# centralBoard.net
KiCad netlist of a schematic drawn in EAGLE
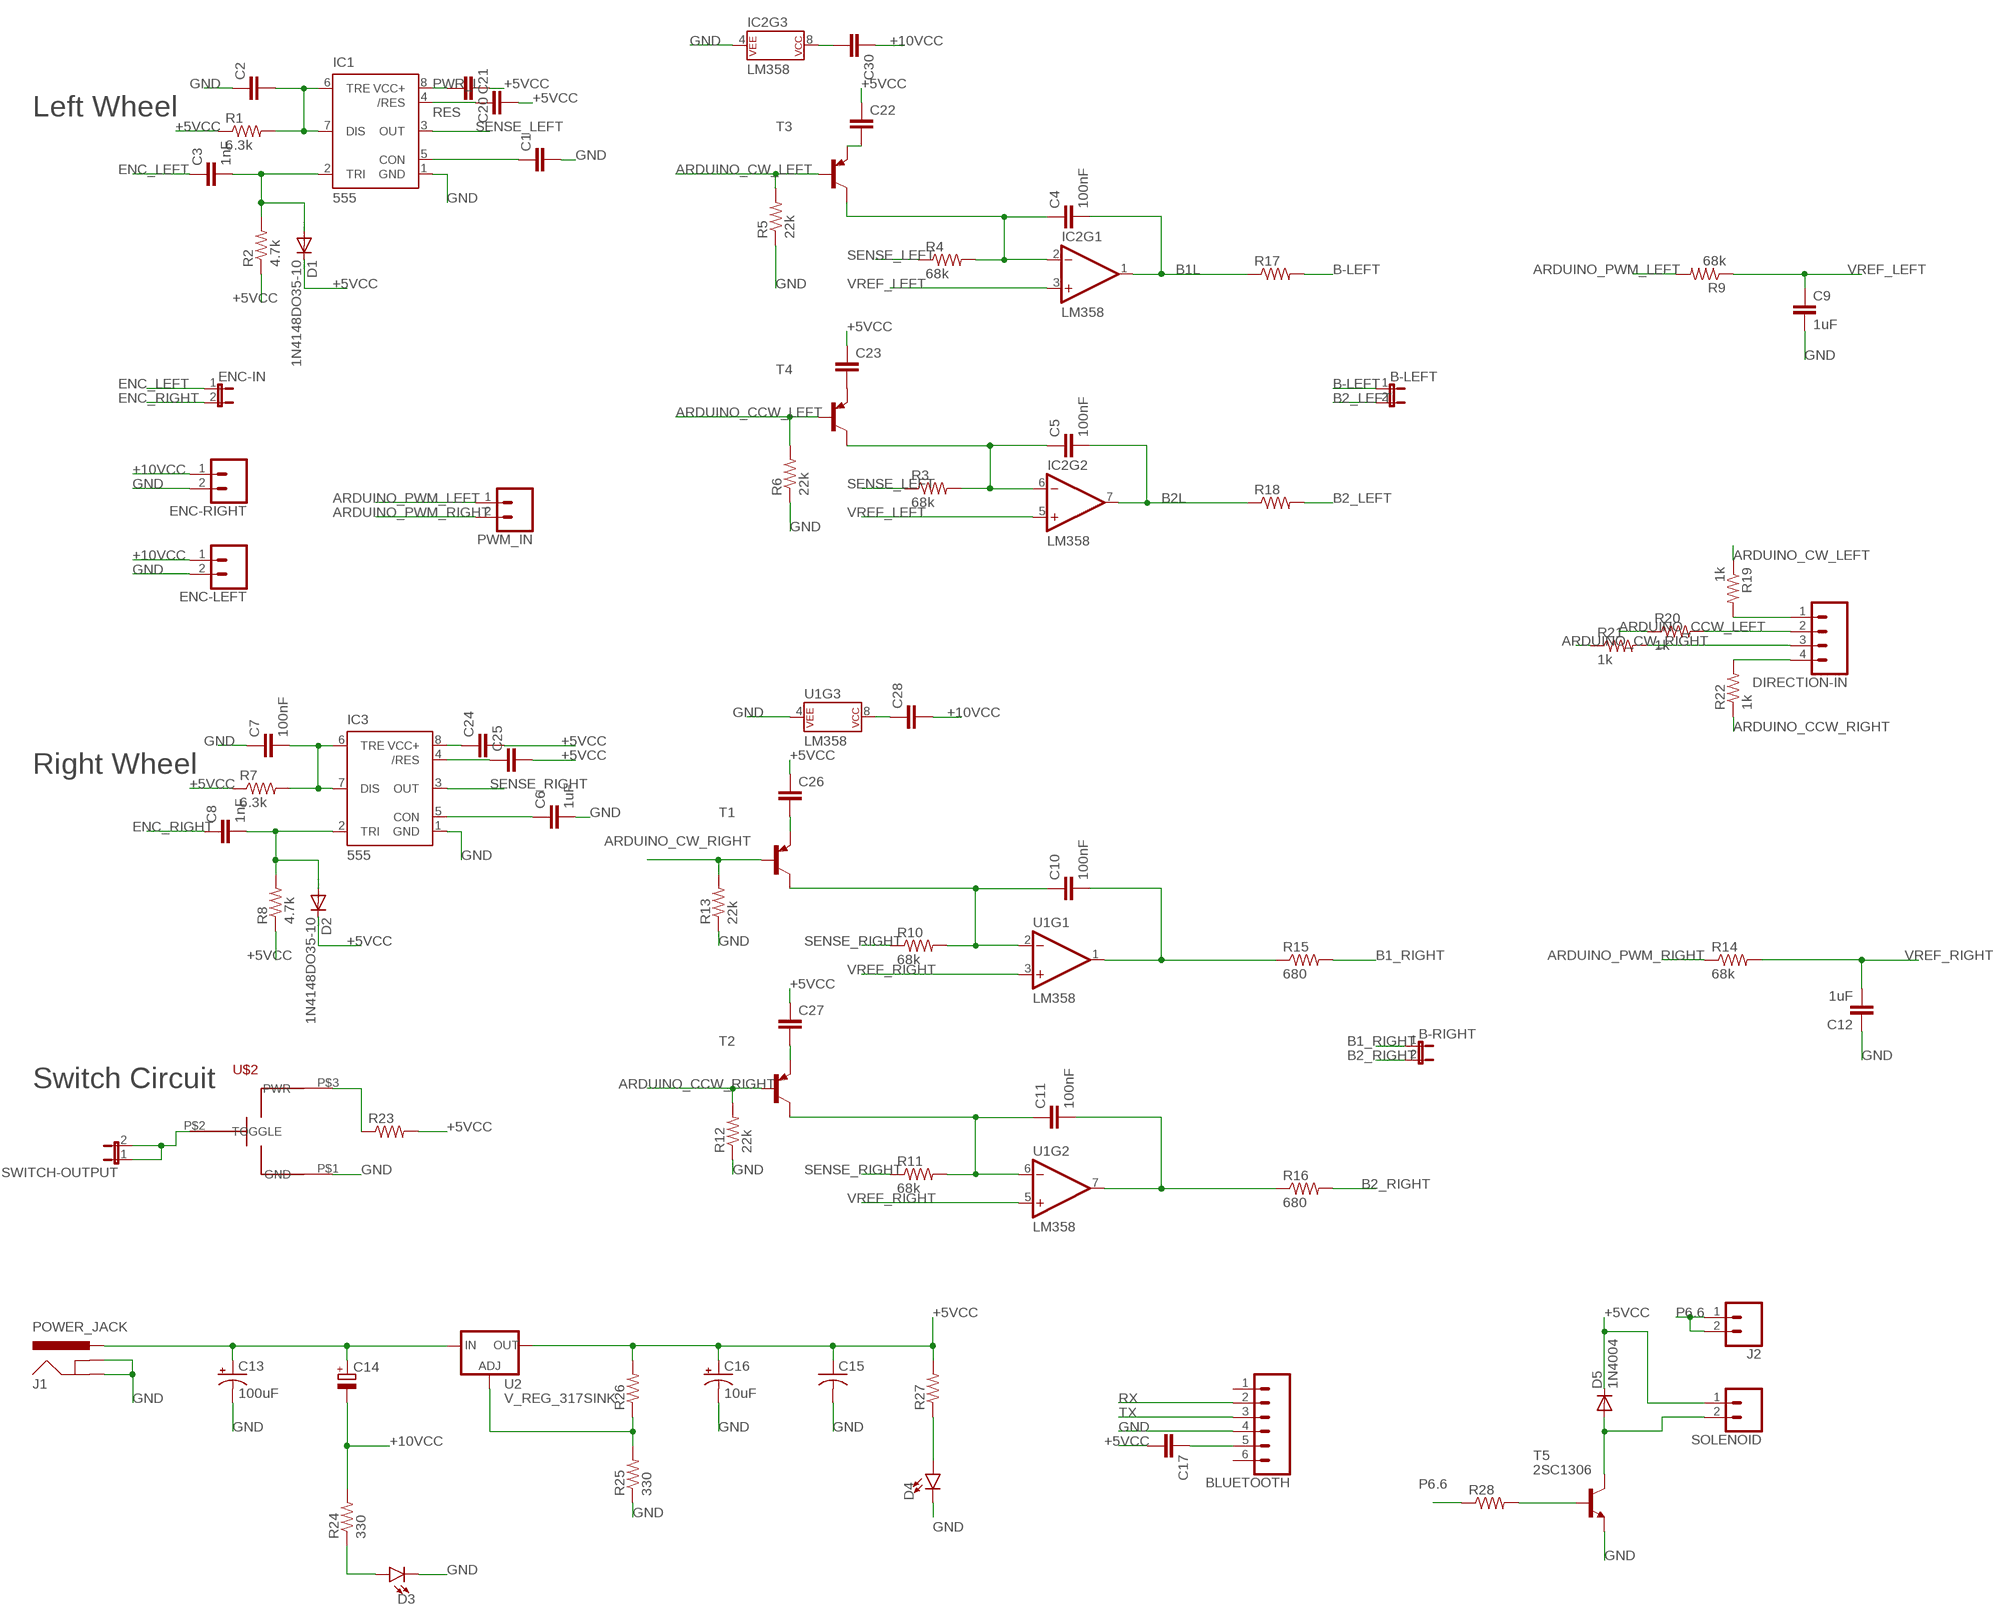
[diagram p0: schematic, sheet 1]

(export (version "E")
  (design (tool "Eeschema 10.0.6"))
  (components
    (comp (ref "B-LEFT")
      (value "JUMPER-2PTH")
      (footprint "eagle-import:1X02")
      (libsource (lib "eagle-import") (part "JUMPER-2PTH"))
    )
    (comp (ref "B-RIGHT")
      (value "JUMPER-2PTH")
      (footprint "eagle-import:1X02")
      (libsource (lib "eagle-import") (part "JUMPER-2PTH"))
    )
    (comp (ref "BLUETOOTH")
      (value "CONN_06SILK_FEMALE_PTH")
      (footprint "eagle-import:1X06")
      (libsource (lib "eagle-import") (part "CONN_06SILK_FEMALE_PTH"))
    )
    (comp (ref "C1")
      (value "C5/2.5")
      (footprint "eagle-import:C5B2.5")
      (libsource (lib "eagle-import") (part "C5/2.5"))
    )
    (comp (ref "C2")
      (value "C5/2.5")
      (footprint "eagle-import:C5B2.5")
      (libsource (lib "eagle-import") (part "C5/2.5"))
    )
    (comp (ref "C3")
      (value "1nF")
      (footprint "eagle-import:C5B2.5")
      (libsource (lib "eagle-import") (part "C5/2.5"))
    )
    (comp (ref "C4")
      (value "100nF")
      (footprint "eagle-import:C5B2.5")
      (libsource (lib "eagle-import") (part "C5/2.5"))
    )
    (comp (ref "C5")
      (value "100nF")
      (footprint "eagle-import:C5B2.5")
      (libsource (lib "eagle-import") (part "C5/2.5"))
    )
    (comp (ref "C6")
      (value "1uF")
      (footprint "eagle-import:C5B2.5")
      (libsource (lib "eagle-import") (part "C5/2.5"))
    )
    (comp (ref "C7")
      (value "100nF")
      (footprint "eagle-import:C5B2.5")
      (libsource (lib "eagle-import") (part "C5/2.5"))
    )
    (comp (ref "C8")
      (value "1nF")
      (footprint "eagle-import:C5B2.5")
      (libsource (lib "eagle-import") (part "C5/2.5"))
    )
    (comp (ref "C9")
      (value "1uF")
      (footprint "eagle-import:C5B2.5")
      (libsource (lib "eagle-import") (part "C5/2.5"))
    )
    (comp (ref "C10")
      (value "100nF")
      (footprint "eagle-import:C5B2.5")
      (libsource (lib "eagle-import") (part "C5/2.5"))
    )
    (comp (ref "C11")
      (value "100nF")
      (footprint "eagle-import:C5B2.5")
      (libsource (lib "eagle-import") (part "C5/2.5"))
    )
    (comp (ref "C12")
      (value "1uF")
      (footprint "eagle-import:C5B2.5")
      (libsource (lib "eagle-import") (part "C5/2.5"))
    )
    (comp (ref "C13")
      (value "100uF")
      (footprint "eagle-import:CPOL-RADIAL-2.5MM-6.5MM")
      (libsource (lib "eagle-import") (part "100UF-POLAR-RADIAL-2.5MM-25V-20%"))
    )
    (comp (ref "C14")
      (value "CPOL-EUE5-6")
      (footprint "eagle-import:E5-6")
      (libsource (lib "eagle-import") (part "CPOL-EUE5-6"))
    )
    (comp (ref "C15")
      (value "C-US050-030X075")
      (footprint "eagle-import:C050-030X075")
      (libsource (lib "eagle-import") (part "C-US050-030X075"))
    )
    (comp (ref "C16")
      (value "10uF")
      (footprint "eagle-import:CPOL-RADIAL-2.5MM-5MM")
      (libsource (lib "eagle-import") (part "10UF-POLAR-RADIAL-2.5MM-25V-20%"))
    )
    (comp (ref "C17")
      (value "C5/3")
      (footprint "eagle-import:C5B3")
      (libsource (lib "eagle-import") (part "C5/3"))
    )
    (comp (ref "C20")
      (value "C5/2.5")
      (footprint "eagle-import:C5B2.5")
      (libsource (lib "eagle-import") (part "C5/2.5"))
    )
    (comp (ref "C21")
      (value "C5/2.5")
      (footprint "eagle-import:C5B2.5")
      (libsource (lib "eagle-import") (part "C5/2.5"))
    )
    (comp (ref "C22")
      (value "C5/2.5")
      (footprint "eagle-import:C5B2.5")
      (libsource (lib "eagle-import") (part "C5/2.5"))
    )
    (comp (ref "C23")
      (value "C5/2.5")
      (footprint "eagle-import:C5B2.5")
      (libsource (lib "eagle-import") (part "C5/2.5"))
    )
    (comp (ref "C24")
      (value "C5/2.5")
      (footprint "eagle-import:C5B2.5")
      (libsource (lib "eagle-import") (part "C5/2.5"))
    )
    (comp (ref "C25")
      (value "C5/2.5")
      (footprint "eagle-import:C5B2.5")
      (libsource (lib "eagle-import") (part "C5/2.5"))
    )
    (comp (ref "C26")
      (value "C5/2.5")
      (footprint "eagle-import:C5B2.5")
      (libsource (lib "eagle-import") (part "C5/2.5"))
    )
    (comp (ref "C27")
      (value "C5/2.5")
      (footprint "eagle-import:C5B2.5")
      (libsource (lib "eagle-import") (part "C5/2.5"))
    )
    (comp (ref "C28")
      (value "C5/2.5")
      (footprint "eagle-import:C5B2.5")
      (libsource (lib "eagle-import") (part "C5/2.5"))
    )
    (comp (ref "C30")
      (value "C5/2.5")
      (footprint "eagle-import:C5B2.5")
      (libsource (lib "eagle-import") (part "C5/2.5"))
    )
    (comp (ref "D1")
      (value "1N4148DO35-10")
      (footprint "eagle-import:DO35-10")
      (libsource (lib "eagle-import") (part "1N4148DO35-10"))
    )
    (comp (ref "D2")
      (value "1N4148DO35-10")
      (footprint "eagle-import:DO35-10")
      (libsource (lib "eagle-import") (part "1N4148DO35-10"))
    )
    (comp (ref "D3")
      (value "LED-RED1206")
      (footprint "eagle-import:LED-1206")
      (libsource (lib "eagle-import") (part "LED-RED1206"))
    )
    (comp (ref "D4")
      (value "LED-RED1206")
      (footprint "eagle-import:LED-1206")
      (libsource (lib "eagle-import") (part "LED-RED1206"))
    )
    (comp (ref "D5")
      (value "1N4004")
      (footprint "eagle-import:DO41-10")
      (libsource (lib "eagle-import") (part "1N4004"))
    )
    (comp (ref "DIRECTION-IN")
      (value "CONN_04")
      (footprint "eagle-import:1X04")
      (libsource (lib "eagle-import") (part "CONN_04"))
    )
    (comp (ref "ENC-IN")
      (value "JUMPER-2PTH")
      (footprint "eagle-import:1X02")
      (libsource (lib "eagle-import") (part "JUMPER-2PTH"))
    )
    (comp (ref "ENC-LEFT")
      (value "CONN_02")
      (footprint "eagle-import:1X02")
      (libsource (lib "eagle-import") (part "CONN_02"))
    )
    (comp (ref "ENC-RIGHT")
      (value "CONN_02")
      (footprint "eagle-import:1X02")
      (libsource (lib "eagle-import") (part "CONN_02"))
    )
    (comp (ref "IC1")
      (value "555")
      (footprint "eagle-import:DIP08-KIT")
      (libsource (lib "eagle-import") (part "555KIT"))
    )
    (comp (ref "IC2")
      (value "LM358")
      (footprint "eagle-import:DIP08")
      (libsource (lib "eagle-import") (part "LM358"))
    )
    (comp (ref "IC3")
      (value "555")
      (footprint "eagle-import:DIP08-KIT")
      (libsource (lib "eagle-import") (part "555KIT"))
    )
    (comp (ref "J1")
      (value "POWER_JACK")
      (footprint "eagle-import:POWER_JACK_PTH")
      (libsource (lib "eagle-import") (part "POWER_JACK"))
    )
    (comp (ref "J2")
      (value "CONN_02")
      (footprint "eagle-import:1X02")
      (libsource (lib "eagle-import") (part "CONN_02"))
    )
    (comp (ref "PWM_IN")
      (value "CONN_02LOCK")
      (footprint "eagle-import:1X02_LOCK")
      (libsource (lib "eagle-import") (part "CONN_02LOCK"))
    )
    (comp (ref "R1")
      (value "6.3k")
      (footprint "eagle-import:0207_10")
      (libsource (lib "eagle-import") (part "R-US_0207/10"))
    )
    (comp (ref "R2")
      (value "4.7k")
      (footprint "eagle-import:0207_10")
      (libsource (lib "eagle-import") (part "R-US_0207/10"))
    )
    (comp (ref "R3")
      (value "68k")
      (footprint "eagle-import:0207_10")
      (libsource (lib "eagle-import") (part "R-US_0207/10"))
    )
    (comp (ref "R4")
      (value "68k")
      (footprint "eagle-import:0207_10")
      (libsource (lib "eagle-import") (part "R-US_0207/10"))
    )
    (comp (ref "R5")
      (value "22k")
      (footprint "eagle-import:0207_10")
      (libsource (lib "eagle-import") (part "R-US_0207/10"))
    )
    (comp (ref "R6")
      (value "22k")
      (footprint "eagle-import:0207_10")
      (libsource (lib "eagle-import") (part "R-US_0207/10"))
    )
    (comp (ref "R7")
      (value "6.3k")
      (footprint "eagle-import:0207_10")
      (libsource (lib "eagle-import") (part "R-US_0207/10"))
    )
    (comp (ref "R8")
      (value "4.7k")
      (footprint "eagle-import:0207_10")
      (libsource (lib "eagle-import") (part "R-US_0207/10"))
    )
    (comp (ref "R9")
      (value "68k")
      (footprint "eagle-import:0207_10")
      (libsource (lib "eagle-import") (part "R-US_0207/10"))
    )
    (comp (ref "R10")
      (value "68k")
      (footprint "eagle-import:0207_10")
      (libsource (lib "eagle-import") (part "R-US_0207/10"))
    )
    (comp (ref "R11")
      (value "68k")
      (footprint "eagle-import:0207_10")
      (libsource (lib "eagle-import") (part "R-US_0207/10"))
    )
    (comp (ref "R12")
      (value "22k")
      (footprint "eagle-import:0207_10")
      (libsource (lib "eagle-import") (part "R-US_0207/10"))
    )
    (comp (ref "R13")
      (value "22k")
      (footprint "eagle-import:0207_10")
      (libsource (lib "eagle-import") (part "R-US_0207/10"))
    )
    (comp (ref "R14")
      (value "68k")
      (footprint "eagle-import:0207_10")
      (libsource (lib "eagle-import") (part "R-US_0207/10"))
    )
    (comp (ref "R15")
      (value "680")
      (footprint "eagle-import:0207_10")
      (libsource (lib "eagle-import") (part "R-US_0207/10"))
    )
    (comp (ref "R16")
      (value "680")
      (footprint "eagle-import:0207_10")
      (libsource (lib "eagle-import") (part "R-US_0207/10"))
    )
    (comp (ref "R17")
      (value "R-US_0207/10")
      (footprint "eagle-import:0207_10")
      (libsource (lib "eagle-import") (part "R-US_0207/10"))
    )
    (comp (ref "R18")
      (value "R-US_0207/10")
      (footprint "eagle-import:0207_10")
      (libsource (lib "eagle-import") (part "R-US_0207/10"))
    )
    (comp (ref "R19")
      (value "1k")
      (footprint "eagle-import:0207_10")
      (libsource (lib "eagle-import") (part "R-US_0207/10"))
    )
    (comp (ref "R20")
      (value "1k")
      (footprint "eagle-import:0207_10")
      (libsource (lib "eagle-import") (part "R-US_0207/10"))
    )
    (comp (ref "R21")
      (value "1k")
      (footprint "eagle-import:0207_10")
      (libsource (lib "eagle-import") (part "R-US_0207/10"))
    )
    (comp (ref "R22")
      (value "1k")
      (footprint "eagle-import:0207_10")
      (libsource (lib "eagle-import") (part "R-US_0207/10"))
    )
    (comp (ref "R23")
      (value "R-US_0207/10")
      (footprint "eagle-import:0207_10")
      (libsource (lib "eagle-import") (part "R-US_0207/10"))
    )
    (comp (ref "R24")
      (value "330")
      (footprint "eagle-import:0207_10")
      (libsource (lib "eagle-import") (part "R-US_0207/10"))
    )
    (comp (ref "R25")
      (value "330")
      (footprint "eagle-import:0207_10")
      (libsource (lib "eagle-import") (part "R-US_0207/10"))
    )
    (comp (ref "R26")
      (value "R-US_0207/10")
      (footprint "eagle-import:0207_10")
      (libsource (lib "eagle-import") (part "R-US_0207/10"))
    )
    (comp (ref "R27")
      (value "R-US_0207/10")
      (footprint "eagle-import:0207_10")
      (libsource (lib "eagle-import") (part "R-US_0207/10"))
    )
    (comp (ref "R28")
      (value "R-US_0207/10")
      (footprint "eagle-import:0207_10")
      (libsource (lib "eagle-import") (part "R-US_0207/10"))
    )
    (comp (ref "SOLENOID")
      (value "CONN_02")
      (footprint "eagle-import:1X02")
      (libsource (lib "eagle-import") (part "CONN_02"))
    )
    (comp (ref "SWITCH-OUTPUT")
      (value "JUMPER-2PTH")
      (footprint "eagle-import:1X02")
      (libsource (lib "eagle-import") (part "JUMPER-2PTH"))
    )
    (comp (ref "T1")
      (value "2N4126-PNP-TO92-CBE")
      (footprint "eagle-import:TO92-CBE")
      (libsource (lib "eagle-import") (part "-PNP-TO92-CBE2N4126"))
    )
    (comp (ref "T2")
      (value "2N4126-PNP-TO92-CBE")
      (footprint "eagle-import:TO92-CBE")
      (libsource (lib "eagle-import") (part "-PNP-TO92-CBE2N4126"))
    )
    (comp (ref "T3")
      (value "2N4126-PNP-TO92-CBE")
      (footprint "eagle-import:TO92-CBE")
      (libsource (lib "eagle-import") (part "-PNP-TO92-CBE2N4126"))
    )
    (comp (ref "T4")
      (value "2N4126-PNP-TO92-CBE")
      (footprint "eagle-import:TO92-CBE")
      (libsource (lib "eagle-import") (part "-PNP-TO92-CBE2N4126"))
    )
    (comp (ref "T5")
      (value "2SC1306")
      (footprint "eagle-import:TO220BV")
      (libsource (lib "eagle-import") (part "2SC1306"))
    )
    (comp (ref "U$2")
      (value "SWITCH")
      (footprint "eagle-import:SWITCH")
      (libsource (lib "eagle-import") (part "SWITCH"))
    )
    (comp (ref "U1")
      (value "LM358")
      (footprint "eagle-import:DIP08")
      (libsource (lib "eagle-import") (part "LM358"))
    )
    (comp (ref "U2")
      (value "V_REG_317SINK")
      (footprint "eagle-import:TO220-ADJ")
      (libsource (lib "eagle-import") (part "V_REG_317SINK"))
    )
  )
  (nets
    (net (code "1") (name "/+5VCC") (class "Default")
      (node (ref "C15") (pin "1") (pinfunction "1_1") (pintype "passive"))
      (node (ref "C16") (pin "1") (pinfunction "+_1") (pintype "passive"))
      (node (ref "C17") (pin "2") (pinfunction "2_2") (pintype "passive"))
      (node (ref "C20") (pin "1") (pinfunction "1_1") (pintype "passive"))
      (node (ref "C21") (pin "2") (pinfunction "2_2") (pintype "passive"))
      (node (ref "C22") (pin "1") (pinfunction "1_1") (pintype "passive"))
      (node (ref "C23") (pin "1") (pinfunction "1_1") (pintype "passive"))
      (node (ref "C24") (pin "2") (pinfunction "2_2") (pintype "passive"))
      (node (ref "C25") (pin "2") (pinfunction "2_2") (pintype "passive"))
      (node (ref "C26") (pin "1") (pinfunction "1_1") (pintype "passive"))
      (node (ref "C27") (pin "1") (pinfunction "1_1") (pintype "passive"))
      (node (ref "D1") (pin "C") (pinfunction "C_C") (pintype "passive"))
      (node (ref "D2") (pin "C") (pinfunction "C_C") (pintype "passive"))
      (node (ref "D5") (pin "C") (pinfunction "C_C") (pintype "passive"))
      (node (ref "R1") (pin "1") (pinfunction "1_1") (pintype "passive"))
      (node (ref "R2") (pin "1") (pinfunction "1_1") (pintype "passive"))
      (node (ref "R23") (pin "2") (pinfunction "2_2") (pintype "passive"))
      (node (ref "R26") (pin "2") (pinfunction "2_2") (pintype "passive"))
      (node (ref "R27") (pin "2") (pinfunction "2_2") (pintype "passive"))
      (node (ref "R7") (pin "1") (pinfunction "1_1") (pintype "passive"))
      (node (ref "R8") (pin "1") (pinfunction "1_1") (pintype "passive"))
      (node (ref "SOLENOID") (pin "1") (pinfunction "1_1") (pintype "passive"))
      (node (ref "U2") (pin "OUT") (pinfunction "OUT_OUT") (pintype "output"))
    )
    (net (code "2") (name "/+10VCC") (class "Default")
      (node (ref "C14") (pin "-") (pinfunction "-_-") (pintype "passive"))
      (node (ref "C28") (pin "2") (pinfunction "2_2") (pintype "passive"))
      (node (ref "C30") (pin "1") (pinfunction "1_1") (pintype "passive"))
      (node (ref "ENC-LEFT") (pin "1") (pinfunction "1_1") (pintype "passive"))
      (node (ref "ENC-RIGHT") (pin "1") (pinfunction "1_1") (pintype "passive"))
      (node (ref "R24") (pin "2") (pinfunction "2_2") (pintype "passive"))
    )
    (net (code "3") (name "/ARDUINO_CCW_LEFT") (class "Default")
      (node (ref "R20") (pin "1") (pinfunction "1_1") (pintype "passive"))
      (node (ref "R6") (pin "2") (pinfunction "2_2") (pintype "passive"))
      (node (ref "T4") (pin "B") (pinfunction "B_B") (pintype "passive"))
    )
    (net (code "4") (name "/ARDUINO_CCW_RIGHT") (class "Default")
      (node (ref "R12") (pin "2") (pinfunction "2_2") (pintype "passive"))
      (node (ref "R22") (pin "1") (pinfunction "1_1") (pintype "passive"))
      (node (ref "T2") (pin "B") (pinfunction "B_B") (pintype "passive"))
    )
    (net (code "5") (name "/ARDUINO_CW_LEFT") (class "Default")
      (node (ref "R19") (pin "1") (pinfunction "1_1") (pintype "passive"))
      (node (ref "R5") (pin "2") (pinfunction "2_2") (pintype "passive"))
      (node (ref "T3") (pin "B") (pinfunction "B_B") (pintype "passive"))
    )
    (net (code "6") (name "/ARDUINO_CW_RIGHT") (class "Default")
      (node (ref "R13") (pin "2") (pinfunction "2_2") (pintype "passive"))
      (node (ref "R21") (pin "1") (pinfunction "1_1") (pintype "passive"))
      (node (ref "T1") (pin "B") (pinfunction "B_B") (pintype "passive"))
    )
    (net (code "7") (name "/ARDUINO_PWM_LEFT") (class "Default")
      (node (ref "PWM_IN") (pin "1") (pinfunction "1_1") (pintype "passive"))
      (node (ref "R9") (pin "2") (pinfunction "2_2") (pintype "passive"))
    )
    (net (code "8") (name "/ARDUINO_PWM_RIGHT") (class "Default")
      (node (ref "PWM_IN") (pin "2") (pinfunction "2_2") (pintype "passive"))
      (node (ref "R14") (pin "1") (pinfunction "1_1") (pintype "passive"))
    )
    (net (code "9") (name "/B-LEFT") (class "Default")
      (node (ref "B-LEFT") (pin "1") (pinfunction "1_1") (pintype "passive"))
      (node (ref "R17") (pin "2") (pinfunction "2_2") (pintype "passive"))
    )
    (net (code "10") (name "/B1L") (class "Default")
      (node (ref "C4") (pin "2") (pinfunction "2_2") (pintype "passive"))
      (node (ref "IC2") (pin "1") (pinfunction "OUT_1") (pintype "output"))
      (node (ref "R17") (pin "1") (pinfunction "1_1") (pintype "passive"))
    )
    (net (code "11") (name "/B1_RIGHT") (class "Default")
      (node (ref "B-RIGHT") (pin "1") (pinfunction "1_1") (pintype "passive"))
      (node (ref "R15") (pin "2") (pinfunction "2_2") (pintype "passive"))
    )
    (net (code "12") (name "/B2L") (class "Default")
      (node (ref "C5") (pin "2") (pinfunction "2_2") (pintype "passive"))
      (node (ref "IC2") (pin "7") (pinfunction "OUT_7") (pintype "output"))
      (node (ref "R18") (pin "1") (pinfunction "1_1") (pintype "passive"))
    )
    (net (code "13") (name "/B2_LEFT") (class "Default")
      (node (ref "B-LEFT") (pin "2") (pinfunction "2_2") (pintype "passive"))
      (node (ref "R18") (pin "2") (pinfunction "2_2") (pintype "passive"))
    )
    (net (code "14") (name "/B2_RIGHT") (class "Default")
      (node (ref "B-RIGHT") (pin "2") (pinfunction "2_2") (pintype "passive"))
      (node (ref "R16") (pin "2") (pinfunction "2_2") (pintype "passive"))
    )
    (net (code "15") (name "/ENC_LEFT") (class "Default")
      (node (ref "C3") (pin "1") (pinfunction "1_1") (pintype "passive"))
      (node (ref "ENC-IN") (pin "1") (pinfunction "1_1") (pintype "passive"))
    )
    (net (code "16") (name "/ENC_RIGHT") (class "Default")
      (node (ref "C8") (pin "1") (pinfunction "1_1") (pintype "passive"))
      (node (ref "ENC-IN") (pin "2") (pinfunction "2_2") (pintype "passive"))
    )
    (net (code "17") (name "/GND") (class "Default")
      (node (ref "BLUETOOTH") (pin "4") (pinfunction "4_4") (pintype "passive"))
      (node (ref "C1") (pin "2") (pinfunction "2_2") (pintype "passive"))
      (node (ref "C12") (pin "1") (pinfunction "1_1") (pintype "passive"))
      (node (ref "C13") (pin "2") (pinfunction "-_2") (pintype "passive"))
      (node (ref "C15") (pin "2") (pinfunction "2_2") (pintype "passive"))
      (node (ref "C16") (pin "2") (pinfunction "-_2") (pintype "passive"))
      (node (ref "C2") (pin "1") (pinfunction "1_1") (pintype "passive"))
      (node (ref "C6") (pin "2") (pinfunction "2_2") (pintype "passive"))
      (node (ref "C7") (pin "1") (pinfunction "1_1") (pintype "passive"))
      (node (ref "C9") (pin "2") (pinfunction "2_2") (pintype "passive"))
      (node (ref "D3") (pin "C") (pinfunction "C_C") (pintype "passive"))
      (node (ref "D4") (pin "C") (pinfunction "C_C") (pintype "passive"))
      (node (ref "ENC-LEFT") (pin "2") (pinfunction "2_2") (pintype "passive"))
      (node (ref "ENC-RIGHT") (pin "2") (pinfunction "2_2") (pintype "passive"))
      (node (ref "IC1") (pin "1") (pinfunction "GND_1") (pintype "power_in"))
      (node (ref "IC2") (pin "4") (pinfunction "P$V-_4") (pintype "bidirectional"))
      (node (ref "IC3") (pin "1") (pinfunction "GND_1") (pintype "power_in"))
      (node (ref "J1") (pin "GND") (pinfunction "GND_GND") (pintype "bidirectional"))
      (node (ref "J1") (pin "GNDBREAK") (pinfunction "GNDBREAK_GNDBREAK") (pintype "bidirectional"))
      (node (ref "R12") (pin "1") (pinfunction "1_1") (pintype "passive"))
      (node (ref "R13") (pin "1") (pinfunction "1_1") (pintype "passive"))
      (node (ref "R25") (pin "1") (pinfunction "1_1") (pintype "passive"))
      (node (ref "R5") (pin "1") (pinfunction "1_1") (pintype "passive"))
      (node (ref "R6") (pin "1") (pinfunction "1_1") (pintype "passive"))
      (node (ref "T5") (pin "3") (pinfunction "E_3") (pintype "passive"))
      (node (ref "U$2") (pin "P$1") (pinfunction "GND_P$1") (pintype "bidirectional"))
      (node (ref "U1") (pin "4") (pinfunction "P$V-_4") (pintype "bidirectional"))
    )
    (net (code "18") (name "/P6.6") (class "Default")
      (node (ref "J2") (pin "1") (pinfunction "1_1") (pintype "passive"))
      (node (ref "J2") (pin "2") (pinfunction "2_2") (pintype "passive"))
      (node (ref "R28") (pin "1") (pinfunction "1_1") (pintype "passive"))
    )
    (net (code "19") (name "/PWR_L") (class "Default")
      (node (ref "C20") (pin "2") (pinfunction "2_2") (pintype "passive"))
      (node (ref "IC1") (pin "8") (pinfunction "VCC+_8") (pintype "power_in"))
    )
    (net (code "20") (name "/RES") (class "Default")
      (node (ref "C21") (pin "1") (pinfunction "1_1") (pintype "passive"))
      (node (ref "IC1") (pin "4") (pinfunction "/RES_4") (pintype "input"))
    )
    (net (code "21") (name "/RX") (class "Default")
      (node (ref "BLUETOOTH") (pin "2") (pinfunction "2_2") (pintype "passive"))
    )
    (net (code "22") (name "/SENSE_LEFT") (class "Default")
      (node (ref "IC1") (pin "3") (pinfunction "OUT_3") (pintype "output"))
      (node (ref "R3") (pin "1") (pinfunction "1_1") (pintype "passive"))
      (node (ref "R4") (pin "1") (pinfunction "1_1") (pintype "passive"))
    )
    (net (code "23") (name "/SENSE_RIGHT") (class "Default")
      (node (ref "IC3") (pin "3") (pinfunction "OUT_3") (pintype "output"))
      (node (ref "R10") (pin "1") (pinfunction "1_1") (pintype "passive"))
      (node (ref "R11") (pin "1") (pinfunction "1_1") (pintype "passive"))
    )
    (net (code "24") (name "/TX") (class "Default")
      (node (ref "BLUETOOTH") (pin "3") (pinfunction "3_3") (pintype "passive"))
    )
    (net (code "25") (name "/VREF_LEFT") (class "Default")
      (node (ref "C9") (pin "1") (pinfunction "1_1") (pintype "passive"))
      (node (ref "IC2") (pin "3") (pinfunction "+IN_3") (pintype "input"))
      (node (ref "IC2") (pin "5") (pinfunction "+IN_5") (pintype "input"))
      (node (ref "R9") (pin "1") (pinfunction "1_1") (pintype "passive"))
    )
    (net (code "26") (name "/VREF_RIGHT") (class "Default")
      (node (ref "C12") (pin "2") (pinfunction "2_2") (pintype "passive"))
      (node (ref "R14") (pin "2") (pinfunction "2_2") (pintype "passive"))
      (node (ref "U1") (pin "3") (pinfunction "+IN_3") (pintype "input"))
      (node (ref "U1") (pin "5") (pinfunction "+IN_5") (pintype "input"))
    )
    (net (code "27") (name "Net-(BLUETOOTH-Pad5)") (class "Default")
      (node (ref "BLUETOOTH") (pin "5") (pinfunction "5_5") (pintype "passive"))
      (node (ref "C17") (pin "1") (pinfunction "1_1") (pintype "passive"))
    )
    (net (code "28") (name "Net-(C13-+)") (class "Default")
      (node (ref "C13") (pin "1") (pinfunction "+_1") (pintype "passive"))
      (node (ref "C14") (pin "+") (pinfunction "+_+") (pintype "passive"))
      (node (ref "J1") (pin "PWR") (pinfunction "PWR_PWR") (pintype "bidirectional"))
      (node (ref "U2") (pin "IN") (pinfunction "IN_IN") (pintype "input"))
    )
    (net (code "29") (name "Net-(C22-Pad2)") (class "Default")
      (node (ref "C22") (pin "2") (pinfunction "2_2") (pintype "passive"))
      (node (ref "T3") (pin "E") (pinfunction "E_E") (pintype "passive"))
    )
    (net (code "30") (name "Net-(C23-Pad2)") (class "Default")
      (node (ref "C23") (pin "2") (pinfunction "2_2") (pintype "passive"))
      (node (ref "T4") (pin "E") (pinfunction "E_E") (pintype "passive"))
    )
    (net (code "31") (name "Net-(C26-Pad2)") (class "Default")
      (node (ref "C26") (pin "2") (pinfunction "2_2") (pintype "passive"))
      (node (ref "T1") (pin "E") (pinfunction "E_E") (pintype "passive"))
    )
    (net (code "32") (name "Net-(C27-Pad2)") (class "Default")
      (node (ref "C27") (pin "2") (pinfunction "2_2") (pintype "passive"))
      (node (ref "T2") (pin "E") (pinfunction "E_E") (pintype "passive"))
    )
    (net (code "33") (name "Net-(D3-PadA)") (class "Default")
      (node (ref "D3") (pin "A") (pinfunction "A_A") (pintype "passive"))
      (node (ref "R24") (pin "1") (pinfunction "1_1") (pintype "passive"))
    )
    (net (code "34") (name "Net-(D4-PadA)") (class "Default")
      (node (ref "D4") (pin "A") (pinfunction "A_A") (pintype "passive"))
      (node (ref "R27") (pin "1") (pinfunction "1_1") (pintype "passive"))
    )
    (net (code "35") (name "Net-(DIRECTION-IN-Pad1)") (class "Default")
      (node (ref "DIRECTION-IN") (pin "1") (pinfunction "1_1") (pintype "passive"))
      (node (ref "R19") (pin "2") (pinfunction "2_2") (pintype "passive"))
    )
    (net (code "36") (name "Net-(DIRECTION-IN-Pad2)") (class "Default")
      (node (ref "DIRECTION-IN") (pin "2") (pinfunction "2_2") (pintype "passive"))
      (node (ref "R20") (pin "2") (pinfunction "2_2") (pintype "passive"))
    )
    (net (code "37") (name "Net-(DIRECTION-IN-Pad3)") (class "Default")
      (node (ref "DIRECTION-IN") (pin "3") (pinfunction "3_3") (pintype "passive"))
      (node (ref "R21") (pin "2") (pinfunction "2_2") (pintype "passive"))
    )
    (net (code "38") (name "Net-(DIRECTION-IN-Pad4)") (class "Default")
      (node (ref "DIRECTION-IN") (pin "4") (pinfunction "4_4") (pintype "passive"))
      (node (ref "R22") (pin "2") (pinfunction "2_2") (pintype "passive"))
    )
    (net (code "39") (name "Net-(IC1-CON)") (class "Default")
      (node (ref "C1") (pin "1") (pinfunction "1_1") (pintype "passive"))
      (node (ref "IC1") (pin "5") (pinfunction "CON_5") (pintype "input"))
    )
    (net (code "40") (name "Net-(IC1-DIS)") (class "Default")
      (node (ref "C2") (pin "2") (pinfunction "2_2") (pintype "passive"))
      (node (ref "IC1") (pin "6") (pinfunction "TRE_6") (pintype "input"))
      (node (ref "IC1") (pin "7") (pinfunction "DIS_7") (pintype "input"))
      (node (ref "R1") (pin "2") (pinfunction "2_2") (pintype "passive"))
    )
    (net (code "41") (name "Net-(IC1-TRI)") (class "Default")
      (node (ref "C3") (pin "2") (pinfunction "2_2") (pintype "passive"))
      (node (ref "D1") (pin "A") (pinfunction "A_A") (pintype "passive"))
      (node (ref "IC1") (pin "2") (pinfunction "TRI_2") (pintype "input"))
      (node (ref "R2") (pin "2") (pinfunction "2_2") (pintype "passive"))
    )
    (net (code "42") (name "Net-(IC2A--IN)") (class "Default")
      (node (ref "C4") (pin "1") (pinfunction "1_1") (pintype "passive"))
      (node (ref "IC2") (pin "2") (pinfunction "-IN_2") (pintype "input"))
      (node (ref "R4") (pin "2") (pinfunction "2_2") (pintype "passive"))
      (node (ref "T3") (pin "C") (pinfunction "C_C") (pintype "passive"))
    )
    (net (code "43") (name "Net-(IC2B--IN)") (class "Default")
      (node (ref "C5") (pin "1") (pinfunction "1_1") (pintype "passive"))
      (node (ref "IC2") (pin "6") (pinfunction "-IN_6") (pintype "input"))
      (node (ref "R3") (pin "2") (pinfunction "2_2") (pintype "passive"))
      (node (ref "T4") (pin "C") (pinfunction "C_C") (pintype "passive"))
    )
    (net (code "44") (name "Net-(IC2C-P$V+)") (class "Default")
      (node (ref "C30") (pin "2") (pinfunction "2_2") (pintype "passive"))
      (node (ref "IC2") (pin "8") (pinfunction "P$V+_8") (pintype "bidirectional"))
    )
    (net (code "45") (name "Net-(IC3-CON)") (class "Default")
      (node (ref "C6") (pin "1") (pinfunction "1_1") (pintype "passive"))
      (node (ref "IC3") (pin "5") (pinfunction "CON_5") (pintype "input"))
    )
    (net (code "46") (name "Net-(IC3-DIS)") (class "Default")
      (node (ref "C7") (pin "2") (pinfunction "2_2") (pintype "passive"))
      (node (ref "IC3") (pin "6") (pinfunction "TRE_6") (pintype "input"))
      (node (ref "IC3") (pin "7") (pinfunction "DIS_7") (pintype "input"))
      (node (ref "R7") (pin "2") (pinfunction "2_2") (pintype "passive"))
    )
    (net (code "47") (name "Net-(IC3-TRI)") (class "Default")
      (node (ref "C8") (pin "2") (pinfunction "2_2") (pintype "passive"))
      (node (ref "D2") (pin "A") (pinfunction "A_A") (pintype "passive"))
      (node (ref "IC3") (pin "2") (pinfunction "TRI_2") (pintype "input"))
      (node (ref "R8") (pin "2") (pinfunction "2_2") (pintype "passive"))
    )
    (net (code "48") (name "Net-(IC3-VCC+)") (class "Default")
      (node (ref "C24") (pin "1") (pinfunction "1_1") (pintype "passive"))
      (node (ref "IC3") (pin "8") (pinfunction "VCC+_8") (pintype "power_in"))
    )
    (net (code "49") (name "Net-(IC3-{slash}RES)") (class "Default")
      (node (ref "C25") (pin "1") (pinfunction "1_1") (pintype "passive"))
      (node (ref "IC3") (pin "4") (pinfunction "/RES_4") (pintype "input"))
    )
    (net (code "50") (name "Net-(R25-Pad2)") (class "Default")
      (node (ref "R25") (pin "2") (pinfunction "2_2") (pintype "passive"))
      (node (ref "R26") (pin "1") (pinfunction "1_1") (pintype "passive"))
      (node (ref "U2") (pin "ADJ") (pinfunction "ADJ_ADJ") (pintype "input"))
    )
    (net (code "51") (name "Net-(T5-B)") (class "Default")
      (node (ref "R28") (pin "2") (pinfunction "2_2") (pintype "passive"))
      (node (ref "T5") (pin "1") (pinfunction "B_1") (pintype "passive"))
    )
    (net (code "52") (name "Net-(T5-C)") (class "Default")
      (node (ref "D5") (pin "A") (pinfunction "A_A") (pintype "passive"))
      (node (ref "SOLENOID") (pin "2") (pinfunction "2_2") (pintype "passive"))
      (node (ref "T5") (pin "2") (pinfunction "C_2") (pintype "passive"))
    )
    (net (code "53") (name "Net-(U$2-PWR)") (class "Default")
      (node (ref "R23") (pin "1") (pinfunction "1_1") (pintype "passive"))
      (node (ref "U$2") (pin "P$3") (pinfunction "PWR_P$3") (pintype "bidirectional"))
    )
    (net (code "54") (name "Net-(U$2-TOGGLE)") (class "Default")
      (node (ref "SWITCH-OUTPUT") (pin "1") (pinfunction "1_1") (pintype "passive"))
      (node (ref "SWITCH-OUTPUT") (pin "2") (pinfunction "2_2") (pintype "passive"))
      (node (ref "U$2") (pin "P$2") (pinfunction "TOGGLE_P$2") (pintype "bidirectional"))
    )
    (net (code "55") (name "Net-(U1A--IN)") (class "Default")
      (node (ref "C10") (pin "1") (pinfunction "1_1") (pintype "passive"))
      (node (ref "R10") (pin "2") (pinfunction "2_2") (pintype "passive"))
      (node (ref "T1") (pin "C") (pinfunction "C_C") (pintype "passive"))
      (node (ref "U1") (pin "2") (pinfunction "-IN_2") (pintype "input"))
    )
    (net (code "56") (name "Net-(U1A-OUT)") (class "Default")
      (node (ref "C10") (pin "2") (pinfunction "2_2") (pintype "passive"))
      (node (ref "R15") (pin "1") (pinfunction "1_1") (pintype "passive"))
      (node (ref "U1") (pin "1") (pinfunction "OUT_1") (pintype "output"))
    )
    (net (code "57") (name "Net-(U1B--IN)") (class "Default")
      (node (ref "C11") (pin "1") (pinfunction "1_1") (pintype "passive"))
      (node (ref "R11") (pin "2") (pinfunction "2_2") (pintype "passive"))
      (node (ref "T2") (pin "C") (pinfunction "C_C") (pintype "passive"))
      (node (ref "U1") (pin "6") (pinfunction "-IN_6") (pintype "input"))
    )
    (net (code "58") (name "Net-(U1B-OUT)") (class "Default")
      (node (ref "C11") (pin "2") (pinfunction "2_2") (pintype "passive"))
      (node (ref "R16") (pin "1") (pinfunction "1_1") (pintype "passive"))
      (node (ref "U1") (pin "7") (pinfunction "OUT_7") (pintype "output"))
    )
    (net (code "59") (name "Net-(U1C-P$V+)") (class "Default")
      (node (ref "C28") (pin "1") (pinfunction "1_1") (pintype "passive"))
      (node (ref "U1") (pin "8") (pinfunction "P$V+_8") (pintype "bidirectional"))
    )
    (net (code "60") (name "unconnected-(BLUETOOTH-Pad1)") (class "Default")
      (node (ref "BLUETOOTH") (pin "1") (pinfunction "1_1") (pintype "passive"))
    )
    (net (code "61") (name "unconnected-(BLUETOOTH-Pad6)") (class "Default")
      (node (ref "BLUETOOTH") (pin "6") (pinfunction "6_6") (pintype "passive"))
    )
  )
)
